# magicmouth-v1_0.net
KiCad netlist of a schematic drawn in EAGLE
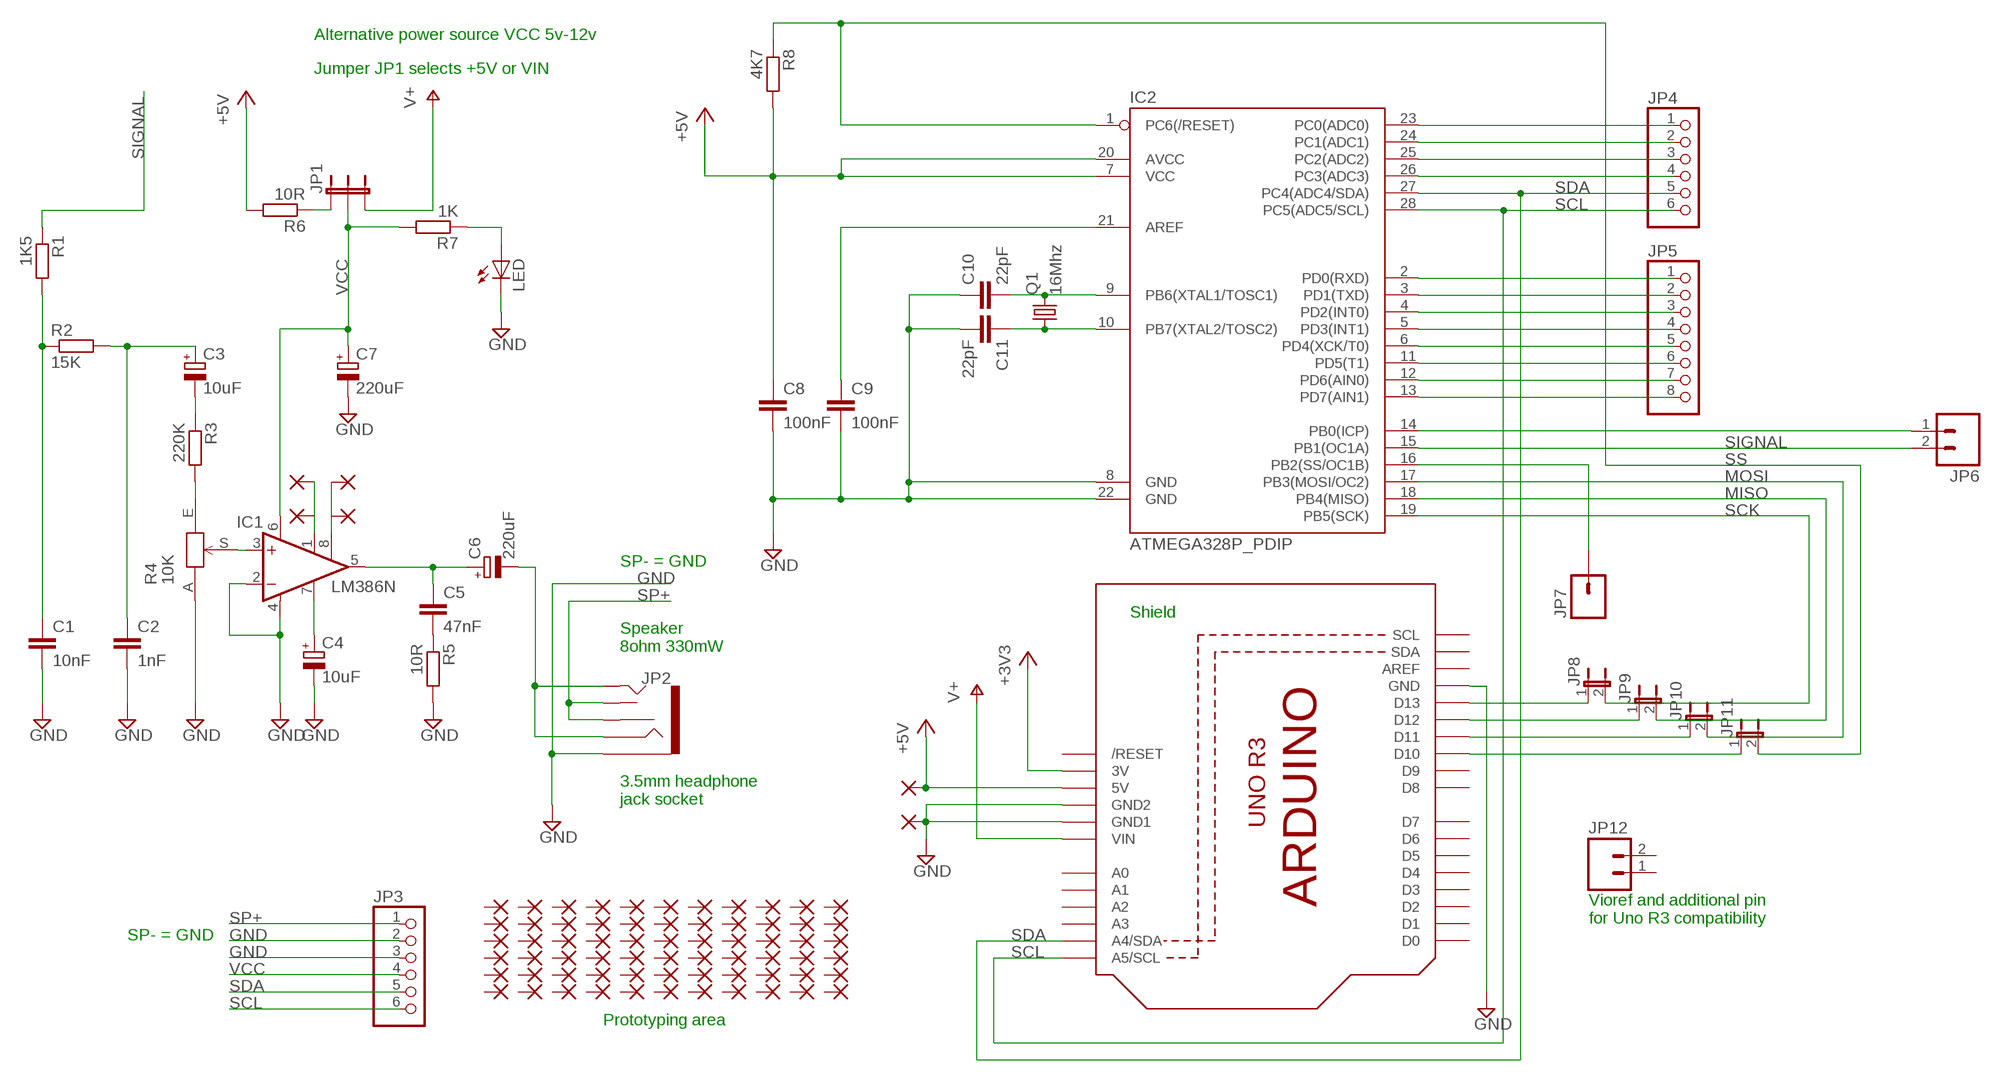
[diagram p0: schematic, sheet 1]

(export (version "E")
  (design (tool "Eeschema 10.0.6"))
  (components
    (comp (ref "C1")
      (value "10nF")
      (footprint "eagle-import:C050-025X075")
      (libsource (lib "eagle-import") (part "C-EU050-025X075"))
    )
    (comp (ref "C2")
      (value "1nF")
      (footprint "eagle-import:C050-025X075")
      (libsource (lib "eagle-import") (part "C-EU050-025X075"))
    )
    (comp (ref "C3")
      (value "10uF")
      (footprint "eagle-import:E2,5-7")
      (libsource (lib "eagle-import") (part "CPOL-EUE2.5-7"))
    )
    (comp (ref "C4")
      (value "10uF")
      (footprint "eagle-import:E2,5-7")
      (libsource (lib "eagle-import") (part "CPOL-EUE2.5-7"))
    )
    (comp (ref "C5")
      (value "47nF")
      (footprint "eagle-import:C050-025X075")
      (libsource (lib "eagle-import") (part "C-EU050-025X075"))
    )
    (comp (ref "C6")
      (value "220uF")
      (footprint "eagle-import:TT2D7")
      (libsource (lib "eagle-import") (part "CPOL-EUTT2D7"))
    )
    (comp (ref "C7")
      (value "220uF")
      (footprint "eagle-import:TT2D7")
      (libsource (lib "eagle-import") (part "CPOL-EUTT2D7"))
    )
    (comp (ref "C8")
      (value "100nF")
      (footprint "eagle-import:C025-025X050")
      (fields (field (name "CAPACITANCE") "10 nF"))
      (libsource (lib "eagle-import") (part "C-EU025-025X050"))
    )
    (comp (ref "C9")
      (value "100nF")
      (footprint "eagle-import:C025-025X050")
      (fields (field (name "CAPACITANCE") "100 nF"))
      (libsource (lib "eagle-import") (part "C-EU025-025X050"))
    )
    (comp (ref "C10")
      (value "22pF")
      (footprint "eagle-import:C025-025X050")
      (fields (field (name "CAPACITANCE") "22 pf"))
      (libsource (lib "eagle-import") (part "C-EU025-025X050"))
    )
    (comp (ref "C11")
      (value "22pF")
      (footprint "eagle-import:C025-025X050")
      (fields (field (name "CAPACITANCE") "22 pf"))
      (libsource (lib "eagle-import") (part "C-EU025-025X050"))
    )
    (comp (ref "IC1")
      (value "LM386N")
      (footprint "eagle-import:DIL08")
      (libsource (lib "eagle-import") (part "LM386?-N1"))
    )
    (comp (ref "IC2")
      (value "ATMEGA328P_PDIP")
      (footprint "eagle-import:DIL28-3")
      (libsource (lib "eagle-import") (part "ATMEGA328P_PDIP"))
    )
    (comp (ref "JP1")
      (value "JUMPER-3PTH")
      (footprint "eagle-import:1X03")
      (libsource (lib "eagle-import") (part "JUMPER-3PTH"))
    )
    (comp (ref "JP2")
      (value "AUDIO-JACK2PTH")
      (footprint "eagle-import:AUDIO-JACK")
      (libsource (lib "eagle-import") (part "AUDIO-JACK2PTH"))
    )
    (comp (ref "JP3")
      (value "PINHD-1X6CB")
      (footprint "eagle-import:1X06-CLEANBIG")
      (libsource (lib "eagle-import") (part "PINHD-1X6CB"))
    )
    (comp (ref "JP4")
      (value "PINHD-1X6CB")
      (footprint "eagle-import:1X06-CLEANBIG")
      (libsource (lib "eagle-import") (part "PINHD-1X6CB"))
    )
    (comp (ref "JP5")
      (value "PINHD-1X8CLEANBIG")
      (footprint "eagle-import:1X08-CLEANBIG")
      (libsource (lib "eagle-import") (part "PINHD-1X8CLEANBIG"))
    )
    (comp (ref "JP6")
      (value "M021X02_NO_SILK")
      (footprint "eagle-import:1X02_NO_SILK")
      (libsource (lib "eagle-import") (part "SparkFun-Connectors_M021X02_NO_SILK"))
    )
    (comp (ref "JP7")
      (value "M01SMDNS")
      (footprint "eagle-import:1X01NS")
      (libsource (lib "eagle-import") (part "M01SMDNS"))
    )
    (comp (ref "JP8")
      (value "JUMPER-2PTH")
      (footprint "eagle-import:1X02")
      (libsource (lib "eagle-import") (part "JUMPER-2PTH"))
    )
    (comp (ref "JP9")
      (value "JUMPER-2PTH")
      (footprint "eagle-import:1X02")
      (libsource (lib "eagle-import") (part "JUMPER-2PTH"))
    )
    (comp (ref "JP10")
      (value "JUMPER-2PTH")
      (footprint "eagle-import:1X02")
      (libsource (lib "eagle-import") (part "JUMPER-2PTH"))
    )
    (comp (ref "JP11")
      (value "JUMPER-2PTH")
      (footprint "eagle-import:1X02")
      (libsource (lib "eagle-import") (part "JUMPER-2PTH"))
    )
    (comp (ref "JP12")
      (value "M021X02_NO_SILK")
      (footprint "eagle-import:1X02_NO_SILK")
      (libsource (lib "eagle-import") (part "M021X02_NO_SILK"))
    )
    (comp (ref "LED")
      (value "LED3MM")
      (footprint "eagle-import:LED3MM")
      (libsource (lib "eagle-import") (part "LED3MM"))
    )
    (comp (ref "PAD1")
      (value "1,6/0,8")
      (footprint "eagle-import:1,6_0,8")
      (libsource (lib "eagle-import") (part "1,6/0,8"))
    )
    (comp (ref "PAD2")
      (value "1,6/0,8")
      (footprint "eagle-import:1,6_0,8")
      (libsource (lib "eagle-import") (part "1,6/0,8"))
    )
    (comp (ref "PAD3")
      (value "1,6/0,8")
      (footprint "eagle-import:1,6_0,8")
      (libsource (lib "eagle-import") (part "1,6/0,8"))
    )
    (comp (ref "PAD4")
      (value "1,6/0,8")
      (footprint "eagle-import:1,6_0,8")
      (libsource (lib "eagle-import") (part "1,6/0,8"))
    )
    (comp (ref "PAD7")
      (value "1,6/0,8")
      (footprint "eagle-import:1,6_0,8")
      (libsource (lib "eagle-import") (part "1,6/0,8"))
    )
    (comp (ref "PAD8")
      (value "1,6/0,8")
      (footprint "eagle-import:1,6_0,8")
      (libsource (lib "eagle-import") (part "1,6/0,8"))
    )
    (comp (ref "PAD9")
      (value "1,6/0,8")
      (footprint "eagle-import:1,6_0,8")
      (libsource (lib "eagle-import") (part "1,6/0,8"))
    )
    (comp (ref "PAD10")
      (value "1,6/0,8")
      (footprint "eagle-import:1,6_0,8")
      (libsource (lib "eagle-import") (part "1,6/0,8"))
    )
    (comp (ref "PAD11")
      (value "1,6/0,8")
      (footprint "eagle-import:1,6_0,8")
      (libsource (lib "eagle-import") (part "1,6/0,8"))
    )
    (comp (ref "PAD12")
      (value "1,6/0,8")
      (footprint "eagle-import:1,6_0,8")
      (libsource (lib "eagle-import") (part "1,6/0,8"))
    )
    (comp (ref "PAD13")
      (value "1,6/0,8")
      (footprint "eagle-import:1,6_0,8")
      (libsource (lib "eagle-import") (part "1,6/0,8"))
    )
    (comp (ref "PAD14")
      (value "1,6/0,8")
      (footprint "eagle-import:1,6_0,8")
      (libsource (lib "eagle-import") (part "1,6/0,8"))
    )
    (comp (ref "PAD15")
      (value "1,6/0,8")
      (footprint "eagle-import:1,6_0,8")
      (libsource (lib "eagle-import") (part "1,6/0,8"))
    )
    (comp (ref "PAD16")
      (value "1,6/0,8")
      (footprint "eagle-import:1,6_0,8")
      (libsource (lib "eagle-import") (part "1,6/0,8"))
    )
    (comp (ref "PAD17")
      (value "1,6/0,8")
      (footprint "eagle-import:1,6_0,8")
      (libsource (lib "eagle-import") (part "1,6/0,8"))
    )
    (comp (ref "PAD18")
      (value "1,6/0,8")
      (footprint "eagle-import:1,6_0,8")
      (libsource (lib "eagle-import") (part "1,6/0,8"))
    )
    (comp (ref "PAD19")
      (value "1,6/0,8")
      (footprint "eagle-import:1,6_0,8")
      (libsource (lib "eagle-import") (part "1,6/0,8"))
    )
    (comp (ref "PAD20")
      (value "1,6/0,8")
      (footprint "eagle-import:1,6_0,8")
      (libsource (lib "eagle-import") (part "1,6/0,8"))
    )
    (comp (ref "PAD21")
      (value "1,6/0,8")
      (footprint "eagle-import:1,6_0,8")
      (libsource (lib "eagle-import") (part "1,6/0,8"))
    )
    (comp (ref "PAD22")
      (value "1,6/0,8")
      (footprint "eagle-import:1,6_0,8")
      (libsource (lib "eagle-import") (part "1,6/0,8"))
    )
    (comp (ref "PAD23")
      (value "1,6/0,8")
      (footprint "eagle-import:1,6_0,8")
      (libsource (lib "eagle-import") (part "1,6/0,8"))
    )
    (comp (ref "PAD24")
      (value "1,6/0,8")
      (footprint "eagle-import:1,6_0,8")
      (libsource (lib "eagle-import") (part "1,6/0,8"))
    )
    (comp (ref "PAD25")
      (value "1,6/0,8")
      (footprint "eagle-import:1,6_0,8")
      (libsource (lib "eagle-import") (part "1,6/0,8"))
    )
    (comp (ref "PAD26")
      (value "1,6/0,8")
      (footprint "eagle-import:1,6_0,8")
      (libsource (lib "eagle-import") (part "1,6/0,8"))
    )
    (comp (ref "PAD27")
      (value "1,6/0,8")
      (footprint "eagle-import:1,6_0,8")
      (libsource (lib "eagle-import") (part "1,6/0,8"))
    )
    (comp (ref "PAD28")
      (value "1,6/0,8")
      (footprint "eagle-import:1,6_0,8")
      (libsource (lib "eagle-import") (part "1,6/0,8"))
    )
    (comp (ref "PAD29")
      (value "1,6/0,8")
      (footprint "eagle-import:1,6_0,8")
      (libsource (lib "eagle-import") (part "1,6/0,8"))
    )
    (comp (ref "PAD30")
      (value "1,6/0,8")
      (footprint "eagle-import:1,6_0,8")
      (libsource (lib "eagle-import") (part "1,6/0,8"))
    )
    (comp (ref "PAD31")
      (value "1,6/0,8")
      (footprint "eagle-import:1,6_0,8")
      (libsource (lib "eagle-import") (part "1,6/0,8"))
    )
    (comp (ref "PAD32")
      (value "1,6/0,8")
      (footprint "eagle-import:1,6_0,8")
      (libsource (lib "eagle-import") (part "1,6/0,8"))
    )
    (comp (ref "PAD33")
      (value "1,6/0,8")
      (footprint "eagle-import:1,6_0,8")
      (libsource (lib "eagle-import") (part "1,6/0,8"))
    )
    (comp (ref "PAD34")
      (value "1,6/0,8")
      (footprint "eagle-import:1,6_0,8")
      (libsource (lib "eagle-import") (part "1,6/0,8"))
    )
    (comp (ref "PAD35")
      (value "1,6/0,8")
      (footprint "eagle-import:1,6_0,8")
      (libsource (lib "eagle-import") (part "1,6/0,8"))
    )
    (comp (ref "PAD36")
      (value "1,6/0,8")
      (footprint "eagle-import:1,6_0,8")
      (libsource (lib "eagle-import") (part "1,6/0,8"))
    )
    (comp (ref "PAD37")
      (value "1,6/0,8")
      (footprint "eagle-import:1,6_0,8")
      (libsource (lib "eagle-import") (part "1,6/0,8"))
    )
    (comp (ref "PAD38")
      (value "1,6/0,8")
      (footprint "eagle-import:1,6_0,8")
      (libsource (lib "eagle-import") (part "1,6/0,8"))
    )
    (comp (ref "PAD39")
      (value "1,6/0,8")
      (footprint "eagle-import:1,6_0,8")
      (libsource (lib "eagle-import") (part "1,6/0,8"))
    )
    (comp (ref "PAD40")
      (value "1,6/0,8")
      (footprint "eagle-import:1,6_0,8")
      (libsource (lib "eagle-import") (part "1,6/0,8"))
    )
    (comp (ref "PAD41")
      (value "1,6/0,8")
      (footprint "eagle-import:1,6_0,8")
      (libsource (lib "eagle-import") (part "1,6/0,8"))
    )
    (comp (ref "PAD42")
      (value "1,6/0,8")
      (footprint "eagle-import:1,6_0,8")
      (libsource (lib "eagle-import") (part "1,6/0,8"))
    )
    (comp (ref "PAD43")
      (value "1,6/0,8")
      (footprint "eagle-import:1,6_0,8")
      (libsource (lib "eagle-import") (part "1,6/0,8"))
    )
    (comp (ref "PAD44")
      (value "1,6/0,8")
      (footprint "eagle-import:1,6_0,8")
      (libsource (lib "eagle-import") (part "1,6/0,8"))
    )
    (comp (ref "PAD45")
      (value "1,6/0,8")
      (footprint "eagle-import:1,6_0,8")
      (libsource (lib "eagle-import") (part "1,6/0,8"))
    )
    (comp (ref "PAD46")
      (value "1,6/0,8")
      (footprint "eagle-import:1,6_0,8")
      (libsource (lib "eagle-import") (part "1,6/0,8"))
    )
    (comp (ref "PAD47")
      (value "1,6/0,8")
      (footprint "eagle-import:1,6_0,8")
      (libsource (lib "eagle-import") (part "1,6/0,8"))
    )
    (comp (ref "PAD48")
      (value "1,6/0,8")
      (footprint "eagle-import:1,6_0,8")
      (libsource (lib "eagle-import") (part "1,6/0,8"))
    )
    (comp (ref "PAD49")
      (value "1,6/0,8")
      (footprint "eagle-import:1,6_0,8")
      (libsource (lib "eagle-import") (part "1,6/0,8"))
    )
    (comp (ref "PAD50")
      (value "1,6/0,8")
      (footprint "eagle-import:1,6_0,8")
      (libsource (lib "eagle-import") (part "1,6/0,8"))
    )
    (comp (ref "PAD51")
      (value "1,6/0,8")
      (footprint "eagle-import:1,6_0,8")
      (libsource (lib "eagle-import") (part "1,6/0,8"))
    )
    (comp (ref "PAD52")
      (value "1,6/0,8")
      (footprint "eagle-import:1,6_0,8")
      (libsource (lib "eagle-import") (part "1,6/0,8"))
    )
    (comp (ref "PAD53")
      (value "1,6/0,8")
      (footprint "eagle-import:1,6_0,8")
      (libsource (lib "eagle-import") (part "1,6/0,8"))
    )
    (comp (ref "PAD54")
      (value "1,6/0,8")
      (footprint "eagle-import:1,6_0,8")
      (libsource (lib "eagle-import") (part "1,6/0,8"))
    )
    (comp (ref "PAD55")
      (value "1,6/0,8")
      (footprint "eagle-import:1,6_0,8")
      (libsource (lib "eagle-import") (part "1,6/0,8"))
    )
    (comp (ref "PAD56")
      (value "1,6/0,8")
      (footprint "eagle-import:1,6_0,8")
      (libsource (lib "eagle-import") (part "1,6/0,8"))
    )
    (comp (ref "PAD57")
      (value "1,6/0,8")
      (footprint "eagle-import:1,6_0,8")
      (libsource (lib "eagle-import") (part "1,6/0,8"))
    )
    (comp (ref "PAD58")
      (value "1,6/0,8")
      (footprint "eagle-import:1,6_0,8")
      (libsource (lib "eagle-import") (part "1,6/0,8"))
    )
    (comp (ref "PAD59")
      (value "1,6/0,8")
      (footprint "eagle-import:1,6_0,8")
      (libsource (lib "eagle-import") (part "1,6/0,8"))
    )
    (comp (ref "PAD60")
      (value "1,6/0,8")
      (footprint "eagle-import:1,6_0,8")
      (libsource (lib "eagle-import") (part "1,6/0,8"))
    )
    (comp (ref "PAD61")
      (value "1,6/0,8")
      (footprint "eagle-import:1,6_0,8")
      (libsource (lib "eagle-import") (part "1,6/0,8"))
    )
    (comp (ref "PAD62")
      (value "1,6/0,8")
      (footprint "eagle-import:1,6_0,8")
      (libsource (lib "eagle-import") (part "1,6/0,8"))
    )
    (comp (ref "PAD63")
      (value "1,6/0,8")
      (footprint "eagle-import:1,6_0,8")
      (libsource (lib "eagle-import") (part "1,6/0,8"))
    )
    (comp (ref "PAD64")
      (value "1,6/0,8")
      (footprint "eagle-import:1,6_0,8")
      (libsource (lib "eagle-import") (part "1,6/0,8"))
    )
    (comp (ref "PAD65")
      (value "1,6/0,8")
      (footprint "eagle-import:1,6_0,8")
      (libsource (lib "eagle-import") (part "1,6/0,8"))
    )
    (comp (ref "PAD66")
      (value "1,6/0,8")
      (footprint "eagle-import:1,6_0,8")
      (libsource (lib "eagle-import") (part "1,6/0,8"))
    )
    (comp (ref "PAD67")
      (value "1,6/0,8")
      (footprint "eagle-import:1,6_0,8")
      (libsource (lib "eagle-import") (part "1,6/0,8"))
    )
    (comp (ref "PAD68")
      (value "1,6/0,8")
      (footprint "eagle-import:1,6_0,8")
      (libsource (lib "eagle-import") (part "1,6/0,8"))
    )
    (comp (ref "PAD69")
      (value "1,6/0,8")
      (footprint "eagle-import:1,6_0,8")
      (libsource (lib "eagle-import") (part "1,6/0,8"))
    )
    (comp (ref "PAD70")
      (value "1,6/0,8")
      (footprint "eagle-import:1,6_0,8")
      (libsource (lib "eagle-import") (part "1,6/0,8"))
    )
    (comp (ref "PAD71")
      (value "1,6/0,8")
      (footprint "eagle-import:1,6_0,8")
      (libsource (lib "eagle-import") (part "1,6/0,8"))
    )
    (comp (ref "PAD72")
      (value "1,6/0,8")
      (footprint "eagle-import:1,6_0,8")
      (libsource (lib "eagle-import") (part "1,6/0,8"))
    )
    (comp (ref "PAD73")
      (value "1,6/0,8")
      (footprint "eagle-import:1,6_0,8")
      (libsource (lib "eagle-import") (part "1,6/0,8"))
    )
    (comp (ref "PAD74")
      (value "1,6/0,8")
      (footprint "eagle-import:1,6_0,8")
      (libsource (lib "eagle-import") (part "1,6/0,8"))
    )
    (comp (ref "Q1")
      (value "16Mhz")
      (footprint "eagle-import:HC49_S")
      (libsource (lib "eagle-import") (part "CRYSTALHC49S"))
    )
    (comp (ref "R1")
      (value "1K5")
      (footprint "eagle-import:0207_7")
      (libsource (lib "eagle-import") (part "R-EU_0207/7"))
    )
    (comp (ref "R2")
      (value "15K")
      (footprint "eagle-import:0207_7")
      (libsource (lib "eagle-import") (part "R-EU_0207/7"))
    )
    (comp (ref "R3")
      (value "220K")
      (footprint "eagle-import:0207_7")
      (libsource (lib "eagle-import") (part "resistor_R-EU_0207/7"))
    )
    (comp (ref "R4")
      (value "10K")
      (footprint "eagle-import:3352T")
      (libsource (lib "eagle-import") (part "TPOT3352"))
    )
    (comp (ref "R5")
      (value "10R")
      (footprint "eagle-import:0207_7")
      (libsource (lib "eagle-import") (part "resistor_R-EU_0207/7"))
    )
    (comp (ref "R6")
      (value "10R")
      (footprint "eagle-import:0207_7")
      (libsource (lib "eagle-import") (part "R-EU_0207/7"))
    )
    (comp (ref "R7")
      (value "1K")
      (footprint "eagle-import:0207_7")
      (libsource (lib "eagle-import") (part "R-EU_0207/7"))
    )
    (comp (ref "R8")
      (value "4K7")
      (footprint "eagle-import:0207_7")
      (fields (field (name "RESISTANCE") "4K7"))
      (libsource (lib "eagle-import") (part "R-EU_0207/7"))
    )
    (comp (ref "U1")
      (value "ARDUINOR3-NOIOREF-NOTEXT")
      (footprint "eagle-import:ARDUINOR3-NOTEXT-NOIOREF")
      (libsource (lib "eagle-import") (part "ARDUINOR3-NOIOREF-NOTEXT"))
    )
  )
  (nets
    (net (code "1") (name "+3V3") (class "Default")
      (node (ref "U1") (pin "3V") (pinfunction "3V_3V") (pintype "power_in"))
    )
    (net (code "2") (name "+5V") (class "Default")
      (node (ref "C8") (pin "1") (pinfunction "1_1") (pintype "passive"))
      (node (ref "IC2") (pin "20") (pinfunction "AVCC_20") (pintype "bidirectional"))
      (node (ref "IC2") (pin "7") (pinfunction "VCC_7") (pintype "bidirectional"))
      (node (ref "PAD55") (pin "1") (pinfunction "P_1") (pintype "passive"))
      (node (ref "R6") (pin "2") (pinfunction "2_2") (pintype "passive"))
      (node (ref "R8") (pin "2") (pinfunction "2_2") (pintype "passive"))
      (node (ref "U1") (pin "5V") (pinfunction "5V_5V") (pintype "power_in"))
    )
    (net (code "3") (name "/MISO") (class "Default")
      (node (ref "IC2") (pin "18") (pinfunction "PB4(MISO)_18") (pintype "bidirectional"))
      (node (ref "JP9") (pin "2") (pinfunction "2_2") (pintype "passive"))
    )
    (net (code "4") (name "/MOSI") (class "Default")
      (node (ref "IC2") (pin "17") (pinfunction "PB3(MOSI/OC2)_17") (pintype "bidirectional"))
      (node (ref "JP10") (pin "2") (pinfunction "2_2") (pintype "passive"))
    )
    (net (code "5") (name "/SCK") (class "Default")
      (node (ref "IC2") (pin "19") (pinfunction "PB5(SCK)_19") (pintype "bidirectional"))
      (node (ref "JP8") (pin "2") (pinfunction "2_2") (pintype "passive"))
    )
    (net (code "6") (name "/SCL") (class "Default")
      (node (ref "IC2") (pin "28") (pinfunction "PC5(ADC5/SCL)_28") (pintype "bidirectional"))
      (node (ref "JP3") (pin "6") (pinfunction "6_6") (pintype "passive"))
      (node (ref "JP4") (pin "6") (pinfunction "6_6") (pintype "passive"))
      (node (ref "U1") (pin "A5") (pinfunction "A5/SCL_A5") (pintype "bidirectional"))
    )
    (net (code "7") (name "/SDA") (class "Default")
      (node (ref "IC2") (pin "27") (pinfunction "PC4(ADC4/SDA)_27") (pintype "bidirectional"))
      (node (ref "JP3") (pin "5") (pinfunction "5_5") (pintype "passive"))
      (node (ref "JP4") (pin "5") (pinfunction "5_5") (pintype "passive"))
      (node (ref "U1") (pin "A4") (pinfunction "A4/SDA_A4") (pintype "bidirectional"))
    )
    (net (code "8") (name "/SIGNAL") (class "Default")
      (node (ref "IC2") (pin "15") (pinfunction "PB1(OC1A)_15") (pintype "bidirectional"))
      (node (ref "JP6") (pin "2") (pinfunction "2_2") (pintype "passive"))
      (node (ref "R1") (pin "1") (pinfunction "1_1") (pintype "passive"))
    )
    (net (code "9") (name "/SP+") (class "Default")
      (node (ref "JP2") (pin "RSH") (pinfunction "RSH_RSH") (pintype "bidirectional"))
      (node (ref "JP2") (pin "TSH") (pinfunction "TSH_TSH") (pintype "bidirectional"))
      (node (ref "JP3") (pin "1") (pinfunction "1_1") (pintype "passive"))
    )
    (net (code "10") (name "/SS") (class "Default")
      (node (ref "IC2") (pin "1") (pinfunction "PC6(/RESET)_1") (pintype "bidirectional"))
      (node (ref "JP11") (pin "2") (pinfunction "2_2") (pintype "passive"))
      (node (ref "R8") (pin "1") (pinfunction "1_1") (pintype "passive"))
    )
    (net (code "11") (name "/VCC") (class "Default")
      (node (ref "C7") (pin "+") (pinfunction "+_+") (pintype "passive"))
      (node (ref "IC1") (pin "6") (pinfunction "VS_6") (pintype "power_in"))
      (node (ref "JP1") (pin "2") (pinfunction "2_2") (pintype "passive"))
      (node (ref "JP3") (pin "4") (pinfunction "4_4") (pintype "passive"))
      (node (ref "R7") (pin "2") (pinfunction "2_2") (pintype "passive"))
    )
    (net (code "12") (name "GND") (class "Default")
      (node (ref "C1") (pin "2") (pinfunction "2_2") (pintype "passive"))
      (node (ref "C10") (pin "1") (pinfunction "1_1") (pintype "passive"))
      (node (ref "C11") (pin "2") (pinfunction "2_2") (pintype "passive"))
      (node (ref "C2") (pin "2") (pinfunction "2_2") (pintype "passive"))
      (node (ref "C4") (pin "-") (pinfunction "-_-") (pintype "passive"))
      (node (ref "C7") (pin "-") (pinfunction "-_-") (pintype "passive"))
      (node (ref "C8") (pin "2") (pinfunction "2_2") (pintype "passive"))
      (node (ref "C9") (pin "2") (pinfunction "2_2") (pintype "passive"))
      (node (ref "IC1") (pin "2") (pinfunction "-IN_2") (pintype "input"))
      (node (ref "IC1") (pin "4") (pinfunction "GND_4") (pintype "power_in"))
      (node (ref "IC2") (pin "22") (pinfunction "GND_22") (pintype "bidirectional"))
      (node (ref "IC2") (pin "8") (pinfunction "GND_8") (pintype "bidirectional"))
      (node (ref "JP2") (pin "SLEEVE") (pinfunction "SLEEVE_SLEEVE") (pintype "bidirectional"))
      (node (ref "JP3") (pin "2") (pinfunction "2_2") (pintype "passive"))
      (node (ref "JP3") (pin "3") (pinfunction "3_3") (pintype "passive"))
      (node (ref "LED") (pin "K") (pinfunction "C_K") (pintype "passive"))
      (node (ref "PAD68") (pin "1") (pinfunction "P_1") (pintype "passive"))
      (node (ref "R4") (pin "A") (pinfunction "A_A") (pintype "passive"))
      (node (ref "R5") (pin "2") (pinfunction "2_2") (pintype "passive"))
      (node (ref "U1") (pin "GND") (pinfunction "GND_GND") (pintype "power_in"))
      (node (ref "U1") (pin "GND1") (pinfunction "GND1_GND1") (pintype "power_in"))
      (node (ref "U1") (pin "GND2") (pinfunction "GND2_GND2") (pintype "power_in"))
    )
    (net (code "13") (name "Net-(C1-Pad1)") (class "Default")
      (node (ref "C1") (pin "1") (pinfunction "1_1") (pintype "passive"))
      (node (ref "R1") (pin "2") (pinfunction "2_2") (pintype "passive"))
      (node (ref "R2") (pin "1") (pinfunction "1_1") (pintype "passive"))
    )
    (net (code "14") (name "Net-(C2-Pad1)") (class "Default")
      (node (ref "C2") (pin "1") (pinfunction "1_1") (pintype "passive"))
      (node (ref "C3") (pin "+") (pinfunction "+_+") (pintype "passive"))
      (node (ref "R2") (pin "2") (pinfunction "2_2") (pintype "passive"))
    )
    (net (code "15") (name "Net-(C3-Pad-)") (class "Default")
      (node (ref "C3") (pin "-") (pinfunction "-_-") (pintype "passive"))
      (node (ref "R3") (pin "1") (pinfunction "1_1") (pintype "passive"))
    )
    (net (code "16") (name "Net-(C5-Pad2)") (class "Default")
      (node (ref "C5") (pin "2") (pinfunction "2_2") (pintype "passive"))
      (node (ref "R5") (pin "1") (pinfunction "1_1") (pintype "passive"))
    )
    (net (code "17") (name "Net-(C6-Pad-)") (class "Default")
      (node (ref "C6") (pin "-") (pinfunction "-_-") (pintype "passive"))
      (node (ref "JP2") (pin "RING") (pinfunction "RING_RING") (pintype "bidirectional"))
      (node (ref "JP2") (pin "TIP") (pinfunction "TIP_TIP") (pintype "bidirectional"))
    )
    (net (code "18") (name "Net-(IC1-+IN)") (class "Default")
      (node (ref "IC1") (pin "3") (pinfunction "+IN_3") (pintype "input"))
      (node (ref "R4") (pin "S") (pinfunction "S_S") (pintype "passive"))
    )
    (net (code "19") (name "Net-(IC1-BYPASS)") (class "Default")
      (node (ref "C4") (pin "+") (pinfunction "+_+") (pintype "passive"))
      (node (ref "IC1") (pin "7") (pinfunction "BYPASS_7") (pintype "passive"))
    )
    (net (code "20") (name "Net-(IC1-OUT)") (class "Default")
      (node (ref "C5") (pin "1") (pinfunction "1_1") (pintype "passive"))
      (node (ref "C6") (pin "+") (pinfunction "+_+") (pintype "passive"))
      (node (ref "IC1") (pin "5") (pinfunction "OUT_5") (pintype "output"))
    )
    (net (code "21") (name "Net-(IC2-AREF)") (class "Default")
      (node (ref "C9") (pin "1") (pinfunction "1_1") (pintype "passive"))
      (node (ref "IC2") (pin "21") (pinfunction "AREF_21") (pintype "bidirectional"))
    )
    (net (code "22") (name "Net-(IC2-PB0(ICP))") (class "Default")
      (node (ref "IC2") (pin "14") (pinfunction "PB0(ICP)_14") (pintype "bidirectional"))
      (node (ref "JP6") (pin "1") (pinfunction "1_1") (pintype "passive"))
    )
    (net (code "23") (name "Net-(IC2-PB2(SS{slash}OC1B))") (class "Default")
      (node (ref "IC2") (pin "16") (pinfunction "PB2(SS/OC1B)_16") (pintype "bidirectional"))
      (node (ref "JP7") (pin "1") (pinfunction "1_1") (pintype "passive"))
    )
    (net (code "24") (name "Net-(IC2-PB6(XTAL1{slash}TOSC1))") (class "Default")
      (node (ref "C10") (pin "2") (pinfunction "2_2") (pintype "passive"))
      (node (ref "IC2") (pin "9") (pinfunction "PB6(XTAL1/TOSC1)_9") (pintype "bidirectional"))
      (node (ref "Q1") (pin "2") (pinfunction "2_2") (pintype "passive"))
    )
    (net (code "25") (name "Net-(IC2-PB7(XTAL2{slash}TOSC2))") (class "Default")
      (node (ref "C11") (pin "1") (pinfunction "1_1") (pintype "passive"))
      (node (ref "IC2") (pin "10") (pinfunction "PB7(XTAL2/TOSC2)_10") (pintype "bidirectional"))
      (node (ref "Q1") (pin "1") (pinfunction "1_1") (pintype "passive"))
    )
    (net (code "26") (name "Net-(IC2-PC0(ADC0))") (class "Default")
      (node (ref "IC2") (pin "23") (pinfunction "PC0(ADC0)_23") (pintype "bidirectional"))
      (node (ref "JP4") (pin "1") (pinfunction "1_1") (pintype "passive"))
    )
    (net (code "27") (name "Net-(IC2-PC1(ADC1))") (class "Default")
      (node (ref "IC2") (pin "24") (pinfunction "PC1(ADC1)_24") (pintype "bidirectional"))
      (node (ref "JP4") (pin "2") (pinfunction "2_2") (pintype "passive"))
    )
    (net (code "28") (name "Net-(IC2-PC2(ADC2))") (class "Default")
      (node (ref "IC2") (pin "25") (pinfunction "PC2(ADC2)_25") (pintype "bidirectional"))
      (node (ref "JP4") (pin "3") (pinfunction "3_3") (pintype "passive"))
    )
    (net (code "29") (name "Net-(IC2-PC3(ADC3))") (class "Default")
      (node (ref "IC2") (pin "26") (pinfunction "PC3(ADC3)_26") (pintype "bidirectional"))
      (node (ref "JP4") (pin "4") (pinfunction "4_4") (pintype "passive"))
    )
    (net (code "30") (name "Net-(IC2-PD0(RXD))") (class "Default")
      (node (ref "IC2") (pin "2") (pinfunction "PD0(RXD)_2") (pintype "bidirectional"))
      (node (ref "JP5") (pin "1") (pinfunction "1_1") (pintype "passive"))
    )
    (net (code "31") (name "Net-(IC2-PD1(TXD))") (class "Default")
      (node (ref "IC2") (pin "3") (pinfunction "PD1(TXD)_3") (pintype "bidirectional"))
      (node (ref "JP5") (pin "2") (pinfunction "2_2") (pintype "passive"))
    )
    (net (code "32") (name "Net-(IC2-PD2(INT0))") (class "Default")
      (node (ref "IC2") (pin "4") (pinfunction "PD2(INT0)_4") (pintype "bidirectional"))
      (node (ref "JP5") (pin "3") (pinfunction "3_3") (pintype "passive"))
    )
    (net (code "33") (name "Net-(IC2-PD3(INT1))") (class "Default")
      (node (ref "IC2") (pin "5") (pinfunction "PD3(INT1)_5") (pintype "bidirectional"))
      (node (ref "JP5") (pin "4") (pinfunction "4_4") (pintype "passive"))
    )
    (net (code "34") (name "Net-(IC2-PD4(XCK{slash}T0))") (class "Default")
      (node (ref "IC2") (pin "6") (pinfunction "PD4(XCK/T0)_6") (pintype "bidirectional"))
      (node (ref "JP5") (pin "5") (pinfunction "5_5") (pintype "passive"))
    )
    (net (code "35") (name "Net-(IC2-PD5(T1))") (class "Default")
      (node (ref "IC2") (pin "11") (pinfunction "PD5(T1)_11") (pintype "bidirectional"))
      (node (ref "JP5") (pin "6") (pinfunction "6_6") (pintype "passive"))
    )
    (net (code "36") (name "Net-(IC2-PD6(AIN0))") (class "Default")
      (node (ref "IC2") (pin "12") (pinfunction "PD6(AIN0)_12") (pintype "bidirectional"))
      (node (ref "JP5") (pin "7") (pinfunction "7_7") (pintype "passive"))
    )
    (net (code "37") (name "Net-(IC2-PD7(AIN1))") (class "Default")
      (node (ref "IC2") (pin "13") (pinfunction "PD7(AIN1)_13") (pintype "bidirectional"))
      (node (ref "JP5") (pin "8") (pinfunction "8_8") (pintype "passive"))
    )
    (net (code "38") (name "Net-(JP1-Pad1)") (class "Default")
      (node (ref "JP1") (pin "1") (pinfunction "1_1") (pintype "passive"))
      (node (ref "R6") (pin "1") (pinfunction "1_1") (pintype "passive"))
    )
    (net (code "39") (name "Net-(JP8-Pad1)") (class "Default")
      (node (ref "JP8") (pin "1") (pinfunction "1_1") (pintype "passive"))
      (node (ref "U1") (pin "D13") (pinfunction "D13_D13") (pintype "bidirectional"))
    )
    (net (code "40") (name "Net-(JP9-Pad1)") (class "Default")
      (node (ref "JP9") (pin "1") (pinfunction "1_1") (pintype "passive"))
      (node (ref "U1") (pin "D12") (pinfunction "D12_D12") (pintype "bidirectional"))
    )
    (net (code "41") (name "Net-(JP10-Pad1)") (class "Default")
      (node (ref "JP10") (pin "1") (pinfunction "1_1") (pintype "passive"))
      (node (ref "U1") (pin "D11") (pinfunction "D11_D11") (pintype "bidirectional"))
    )
    (net (code "42") (name "Net-(JP11-Pad1)") (class "Default")
      (node (ref "JP11") (pin "1") (pinfunction "1_1") (pintype "passive"))
      (node (ref "U1") (pin "D10") (pinfunction "D10_D10") (pintype "bidirectional"))
    )
    (net (code "43") (name "Net-(LED-PadA)") (class "Default")
      (node (ref "LED") (pin "A") (pinfunction "A_A") (pintype "passive"))
      (node (ref "R7") (pin "1") (pinfunction "1_1") (pintype "passive"))
    )
    (net (code "44") (name "Net-(PAD1-P)") (class "Default")
      (node (ref "IC1") (pin "1") (pinfunction "GAIN_1") (pintype "passive"))
      (node (ref "PAD1") (pin "1") (pinfunction "P_1") (pintype "passive"))
      (node (ref "PAD2") (pin "1") (pinfunction "P_1") (pintype "passive"))
    )
    (net (code "45") (name "Net-(PAD3-P)") (class "Default")
      (node (ref "IC1") (pin "8") (pinfunction "GAIN_8") (pintype "passive"))
      (node (ref "PAD3") (pin "1") (pinfunction "P_1") (pintype "passive"))
      (node (ref "PAD4") (pin "1") (pinfunction "P_1") (pintype "passive"))
    )
    (net (code "46") (name "Net-(R3-Pad2)") (class "Default")
      (node (ref "R3") (pin "2") (pinfunction "2_2") (pintype "passive"))
      (node (ref "R4") (pin "E") (pinfunction "E_E") (pintype "passive"))
    )
    (net (code "47") (name "V+") (class "Default")
      (node (ref "JP1") (pin "3") (pinfunction "3_3") (pintype "passive"))
      (node (ref "U1") (pin "VIN") (pinfunction "VIN_VIN") (pintype "power_in"))
    )
    (net (code "48") (name "unconnected-(JP12-Pad1)") (class "Default")
      (node (ref "JP12") (pin "1") (pinfunction "1_1") (pintype "passive"))
    )
    (net (code "49") (name "unconnected-(JP12-Pad2)") (class "Default")
      (node (ref "JP12") (pin "2") (pinfunction "2_2") (pintype "passive"))
    )
    (net (code "50") (name "unconnected-(PAD7-P-Pad1)") (class "Default")
      (node (ref "PAD7") (pin "1") (pinfunction "P_1") (pintype "passive"))
    )
    (net (code "51") (name "unconnected-(PAD8-P-Pad1)") (class "Default")
      (node (ref "PAD8") (pin "1") (pinfunction "P_1") (pintype "passive"))
    )
    (net (code "52") (name "unconnected-(PAD9-P-Pad1)") (class "Default")
      (node (ref "PAD9") (pin "1") (pinfunction "P_1") (pintype "passive"))
    )
    (net (code "53") (name "unconnected-(PAD10-P-Pad1)") (class "Default")
      (node (ref "PAD10") (pin "1") (pinfunction "P_1") (pintype "passive"))
    )
    (net (code "54") (name "unconnected-(PAD11-P-Pad1)") (class "Default")
      (node (ref "PAD11") (pin "1") (pinfunction "P_1") (pintype "passive"))
    )
    (net (code "55") (name "unconnected-(PAD12-P-Pad1)") (class "Default")
      (node (ref "PAD12") (pin "1") (pinfunction "P_1") (pintype "passive"))
    )
    (net (code "56") (name "unconnected-(PAD13-P-Pad1)") (class "Default")
      (node (ref "PAD13") (pin "1") (pinfunction "P_1") (pintype "passive"))
    )
    (net (code "57") (name "unconnected-(PAD14-P-Pad1)") (class "Default")
      (node (ref "PAD14") (pin "1") (pinfunction "P_1") (pintype "passive"))
    )
    (net (code "58") (name "unconnected-(PAD15-P-Pad1)") (class "Default")
      (node (ref "PAD15") (pin "1") (pinfunction "P_1") (pintype "passive"))
    )
    (net (code "59") (name "unconnected-(PAD16-P-Pad1)") (class "Default")
      (node (ref "PAD16") (pin "1") (pinfunction "P_1") (pintype "passive"))
    )
    (net (code "60") (name "unconnected-(PAD17-P-Pad1)") (class "Default")
      (node (ref "PAD17") (pin "1") (pinfunction "P_1") (pintype "passive"))
    )
    (net (code "61") (name "unconnected-(PAD18-P-Pad1)") (class "Default")
      (node (ref "PAD18") (pin "1") (pinfunction "P_1") (pintype "passive"))
    )
    (net (code "62") (name "unconnected-(PAD19-P-Pad1)") (class "Default")
      (node (ref "PAD19") (pin "1") (pinfunction "P_1") (pintype "passive"))
    )
    (net (code "63") (name "unconnected-(PAD20-P-Pad1)") (class "Default")
      (node (ref "PAD20") (pin "1") (pinfunction "P_1") (pintype "passive"))
    )
    (net (code "64") (name "unconnected-(PAD21-P-Pad1)") (class "Default")
      (node (ref "PAD21") (pin "1") (pinfunction "P_1") (pintype "passive"))
    )
    (net (code "65") (name "unconnected-(PAD22-P-Pad1)") (class "Default")
      (node (ref "PAD22") (pin "1") (pinfunction "P_1") (pintype "passive"))
    )
    (net (code "66") (name "unconnected-(PAD23-P-Pad1)") (class "Default")
      (node (ref "PAD23") (pin "1") (pinfunction "P_1") (pintype "passive"))
    )
    (net (code "67") (name "unconnected-(PAD24-P-Pad1)") (class "Default")
      (node (ref "PAD24") (pin "1") (pinfunction "P_1") (pintype "passive"))
    )
    (net (code "68") (name "unconnected-(PAD25-P-Pad1)") (class "Default")
      (node (ref "PAD25") (pin "1") (pinfunction "P_1") (pintype "passive"))
    )
    (net (code "69") (name "unconnected-(PAD26-P-Pad1)") (class "Default")
      (node (ref "PAD26") (pin "1") (pinfunction "P_1") (pintype "passive"))
    )
    (net (code "70") (name "unconnected-(PAD27-P-Pad1)") (class "Default")
      (node (ref "PAD27") (pin "1") (pinfunction "P_1") (pintype "passive"))
    )
    (net (code "71") (name "unconnected-(PAD28-P-Pad1)") (class "Default")
      (node (ref "PAD28") (pin "1") (pinfunction "P_1") (pintype "passive"))
    )
    (net (code "72") (name "unconnected-(PAD29-P-Pad1)") (class "Default")
      (node (ref "PAD29") (pin "1") (pinfunction "P_1") (pintype "passive"))
    )
    (net (code "73") (name "unconnected-(PAD30-P-Pad1)") (class "Default")
      (node (ref "PAD30") (pin "1") (pinfunction "P_1") (pintype "passive"))
    )
    (net (code "74") (name "unconnected-(PAD31-P-Pad1)") (class "Default")
      (node (ref "PAD31") (pin "1") (pinfunction "P_1") (pintype "passive"))
    )
    (net (code "75") (name "unconnected-(PAD32-P-Pad1)") (class "Default")
      (node (ref "PAD32") (pin "1") (pinfunction "P_1") (pintype "passive"))
    )
    (net (code "76") (name "unconnected-(PAD33-P-Pad1)") (class "Default")
      (node (ref "PAD33") (pin "1") (pinfunction "P_1") (pintype "passive"))
    )
    (net (code "77") (name "unconnected-(PAD34-P-Pad1)") (class "Default")
      (node (ref "PAD34") (pin "1") (pinfunction "P_1") (pintype "passive"))
    )
    (net (code "78") (name "unconnected-(PAD35-P-Pad1)") (class "Default")
      (node (ref "PAD35") (pin "1") (pinfunction "P_1") (pintype "passive"))
    )
    (net (code "79") (name "unconnected-(PAD36-P-Pad1)") (class "Default")
      (node (ref "PAD36") (pin "1") (pinfunction "P_1") (pintype "passive"))
    )
    (net (code "80") (name "unconnected-(PAD37-P-Pad1)") (class "Default")
      (node (ref "PAD37") (pin "1") (pinfunction "P_1") (pintype "passive"))
    )
    (net (code "81") (name "unconnected-(PAD38-P-Pad1)") (class "Default")
      (node (ref "PAD38") (pin "1") (pinfunction "P_1") (pintype "passive"))
    )
    (net (code "82") (name "unconnected-(PAD39-P-Pad1)") (class "Default")
      (node (ref "PAD39") (pin "1") (pinfunction "P_1") (pintype "passive"))
    )
    (net (code "83") (name "unconnected-(PAD40-P-Pad1)") (class "Default")
      (node (ref "PAD40") (pin "1") (pinfunction "P_1") (pintype "passive"))
    )
    (net (code "84") (name "unconnected-(PAD41-P-Pad1)") (class "Default")
      (node (ref "PAD41") (pin "1") (pinfunction "P_1") (pintype "passive"))
    )
    (net (code "85") (name "unconnected-(PAD42-P-Pad1)") (class "Default")
      (node (ref "PAD42") (pin "1") (pinfunction "P_1") (pintype "passive"))
    )
    (net (code "86") (name "unconnected-(PAD43-P-Pad1)") (class "Default")
      (node (ref "PAD43") (pin "1") (pinfunction "P_1") (pintype "passive"))
    )
    (net (code "87") (name "unconnected-(PAD44-P-Pad1)") (class "Default")
      (node (ref "PAD44") (pin "1") (pinfunction "P_1") (pintype "passive"))
    )
    (net (code "88") (name "unconnected-(PAD45-P-Pad1)") (class "Default")
      (node (ref "PAD45") (pin "1") (pinfunction "P_1") (pintype "passive"))
    )
    (net (code "89") (name "unconnected-(PAD46-P-Pad1)") (class "Default")
      (node (ref "PAD46") (pin "1") (pinfunction "P_1") (pintype "passive"))
    )
    (net (code "90") (name "unconnected-(PAD47-P-Pad1)") (class "Default")
      (node (ref "PAD47") (pin "1") (pinfunction "P_1") (pintype "passive"))
    )
    (net (code "91") (name "unconnected-(PAD48-P-Pad1)") (class "Default")
      (node (ref "PAD48") (pin "1") (pinfunction "P_1") (pintype "passive"))
    )
    (net (code "92") (name "unconnected-(PAD49-P-Pad1)") (class "Default")
      (node (ref "PAD49") (pin "1") (pinfunction "P_1") (pintype "passive"))
    )
    (net (code "93") (name "unconnected-(PAD50-P-Pad1)") (class "Default")
      (node (ref "PAD50") (pin "1") (pinfunction "P_1") (pintype "passive"))
    )
    (net (code "94") (name "unconnected-(PAD51-P-Pad1)") (class "Default")
      (node (ref "PAD51") (pin "1") (pinfunction "P_1") (pintype "passive"))
    )
    (net (code "95") (name "unconnected-(PAD52-P-Pad1)") (class "Default")
      (node (ref "PAD52") (pin "1") (pinfunction "P_1") (pintype "passive"))
    )
    (net (code "96") (name "unconnected-(PAD53-P-Pad1)") (class "Default")
      (node (ref "PAD53") (pin "1") (pinfunction "P_1") (pintype "passive"))
    )
    (net (code "97") (name "unconnected-(PAD54-P-Pad1)") (class "Default")
      (node (ref "PAD54") (pin "1") (pinfunction "P_1") (pintype "passive"))
    )
    (net (code "98") (name "unconnected-(PAD56-P-Pad1)") (class "Default")
      (node (ref "PAD56") (pin "1") (pinfunction "P_1") (pintype "passive"))
    )
    (net (code "99") (name "unconnected-(PAD57-P-Pad1)") (class "Default")
      (node (ref "PAD57") (pin "1") (pinfunction "P_1") (pintype "passive"))
    )
    (net (code "100") (name "unconnected-(PAD58-P-Pad1)") (class "Default")
      (node (ref "PAD58") (pin "1") (pinfunction "P_1") (pintype "passive"))
    )
    (net (code "101") (name "unconnected-(PAD59-P-Pad1)") (class "Default")
      (node (ref "PAD59") (pin "1") (pinfunction "P_1") (pintype "passive"))
    )
    (net (code "102") (name "unconnected-(PAD60-P-Pad1)") (class "Default")
      (node (ref "PAD60") (pin "1") (pinfunction "P_1") (pintype "passive"))
    )
    (net (code "103") (name "unconnected-(PAD61-P-Pad1)") (class "Default")
      (node (ref "PAD61") (pin "1") (pinfunction "P_1") (pintype "passive"))
    )
    (net (code "104") (name "unconnected-(PAD62-P-Pad1)") (class "Default")
      (node (ref "PAD62") (pin "1") (pinfunction "P_1") (pintype "passive"))
    )
    (net (code "105") (name "unconnected-(PAD63-P-Pad1)") (class "Default")
      (node (ref "PAD63") (pin "1") (pinfunction "P_1") (pintype "passive"))
    )
    (net (code "106") (name "unconnected-(PAD64-P-Pad1)") (class "Default")
      (node (ref "PAD64") (pin "1") (pinfunction "P_1") (pintype "passive"))
    )
    (net (code "107") (name "unconnected-(PAD65-P-Pad1)") (class "Default")
      (node (ref "PAD65") (pin "1") (pinfunction "P_1") (pintype "passive"))
    )
    (net (code "108") (name "unconnected-(PAD66-P-Pad1)") (class "Default")
      (node (ref "PAD66") (pin "1") (pinfunction "P_1") (pintype "passive"))
    )
    (net (code "109") (name "unconnected-(PAD67-P-Pad1)") (class "Default")
      (node (ref "PAD67") (pin "1") (pinfunction "P_1") (pintype "passive"))
    )
    (net (code "110") (name "unconnected-(PAD69-P-Pad1)") (class "Default")
      (node (ref "PAD69") (pin "1") (pinfunction "P_1") (pintype "passive"))
    )
    (net (code "111") (name "unconnected-(PAD70-P-Pad1)") (class "Default")
      (node (ref "PAD70") (pin "1") (pinfunction "P_1") (pintype "passive"))
    )
    (net (code "112") (name "unconnected-(PAD71-P-Pad1)") (class "Default")
      (node (ref "PAD71") (pin "1") (pinfunction "P_1") (pintype "passive"))
    )
    (net (code "113") (name "unconnected-(PAD72-P-Pad1)") (class "Default")
      (node (ref "PAD72") (pin "1") (pinfunction "P_1") (pintype "passive"))
    )
    (net (code "114") (name "unconnected-(PAD73-P-Pad1)") (class "Default")
      (node (ref "PAD73") (pin "1") (pinfunction "P_1") (pintype "passive"))
    )
    (net (code "115") (name "unconnected-(PAD74-P-Pad1)") (class "Default")
      (node (ref "PAD74") (pin "1") (pinfunction "P_1") (pintype "passive"))
    )
    (net (code "116") (name "unconnected-(U1-PadA0)") (class "Default")
      (node (ref "U1") (pin "A0") (pinfunction "A0_A0") (pintype "bidirectional"))
    )
    (net (code "117") (name "unconnected-(U1-PadA1)") (class "Default")
      (node (ref "U1") (pin "A1") (pinfunction "A1_A1") (pintype "bidirectional"))
    )
    (net (code "118") (name "unconnected-(U1-PadA2)") (class "Default")
      (node (ref "U1") (pin "A2") (pinfunction "A2_A2") (pintype "bidirectional"))
    )
    (net (code "119") (name "unconnected-(U1-PadA3)") (class "Default")
      (node (ref "U1") (pin "A3") (pinfunction "A3_A3") (pintype "bidirectional"))
    )
    (net (code "120") (name "unconnected-(U1-PadAREF)") (class "Default")
      (node (ref "U1") (pin "AREF") (pinfunction "AREF_AREF") (pintype "bidirectional"))
    )
    (net (code "121") (name "unconnected-(U1-PadD0)") (class "Default")
      (node (ref "U1") (pin "D0") (pinfunction "D0_D0") (pintype "bidirectional"))
    )
    (net (code "122") (name "unconnected-(U1-PadD1)") (class "Default")
      (node (ref "U1") (pin "D1") (pinfunction "D1_D1") (pintype "bidirectional"))
    )
    (net (code "123") (name "unconnected-(U1-PadD2)") (class "Default")
      (node (ref "U1") (pin "D2") (pinfunction "D2_D2") (pintype "bidirectional"))
    )
    (net (code "124") (name "unconnected-(U1-PadD3)") (class "Default")
      (node (ref "U1") (pin "D3") (pinfunction "D3_D3") (pintype "bidirectional"))
    )
    (net (code "125") (name "unconnected-(U1-PadD4)") (class "Default")
      (node (ref "U1") (pin "D4") (pinfunction "D4_D4") (pintype "bidirectional"))
    )
    (net (code "126") (name "unconnected-(U1-PadD5)") (class "Default")
      (node (ref "U1") (pin "D5") (pinfunction "D5_D5") (pintype "bidirectional"))
    )
    (net (code "127") (name "unconnected-(U1-PadD6)") (class "Default")
      (node (ref "U1") (pin "D6") (pinfunction "D6_D6") (pintype "bidirectional"))
    )
    (net (code "128") (name "unconnected-(U1-PadD7)") (class "Default")
      (node (ref "U1") (pin "D7") (pinfunction "D7_D7") (pintype "bidirectional"))
    )
    (net (code "129") (name "unconnected-(U1-PadD8)") (class "Default")
      (node (ref "U1") (pin "D8") (pinfunction "D8_D8") (pintype "bidirectional"))
    )
    (net (code "130") (name "unconnected-(U1-PadD9)") (class "Default")
      (node (ref "U1") (pin "D9") (pinfunction "D9_D9") (pintype "bidirectional"))
    )
    (net (code "131") (name "unconnected-(U1-PadSCL)") (class "Default")
      (node (ref "U1") (pin "SCL") (pinfunction "SCL_SCL") (pintype "bidirectional"))
    )
    (net (code "132") (name "unconnected-(U1-PadSDA)") (class "Default")
      (node (ref "U1") (pin "SDA") (pinfunction "SDA_SDA") (pintype "bidirectional"))
    )
    (net (code "133") (name "unconnected-(U1-{slash}RESET-PadRESET)") (class "Default")
      (node (ref "U1") (pin "RESET") (pinfunction "/RESET_RESET") (pintype "bidirectional"))
    )
  )
)
